# Lab_Controller_Board_v09.net
KiCad netlist of a schematic drawn in EAGLE
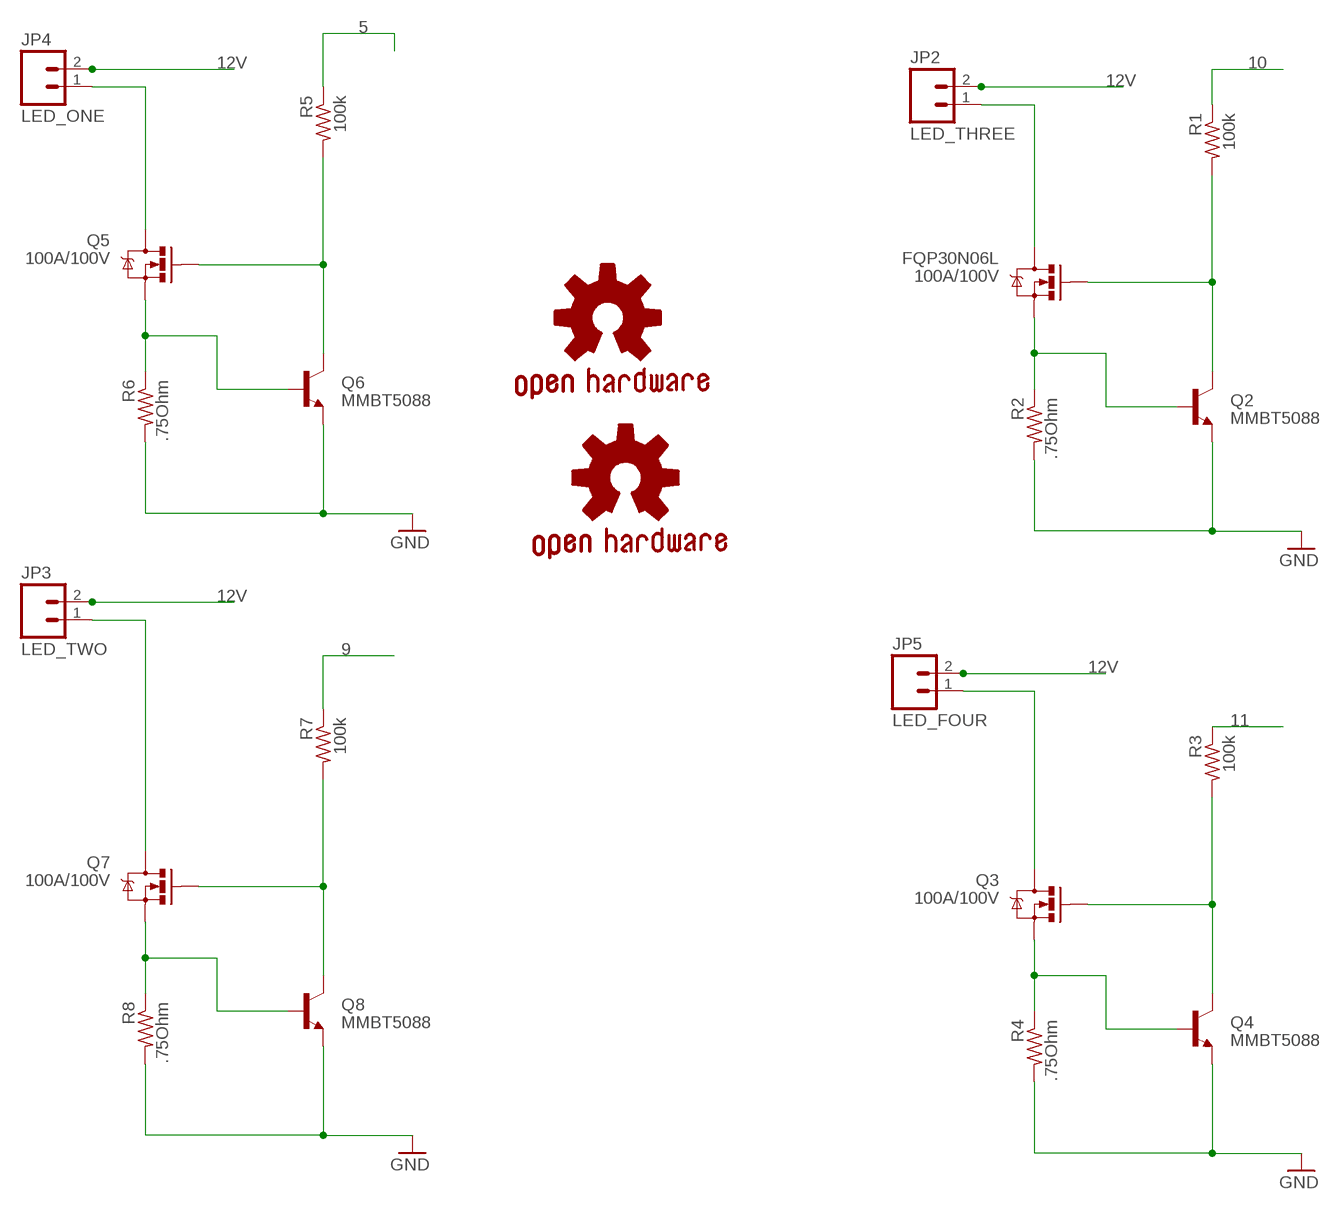
[diagram p0: schematic, sheet 1]
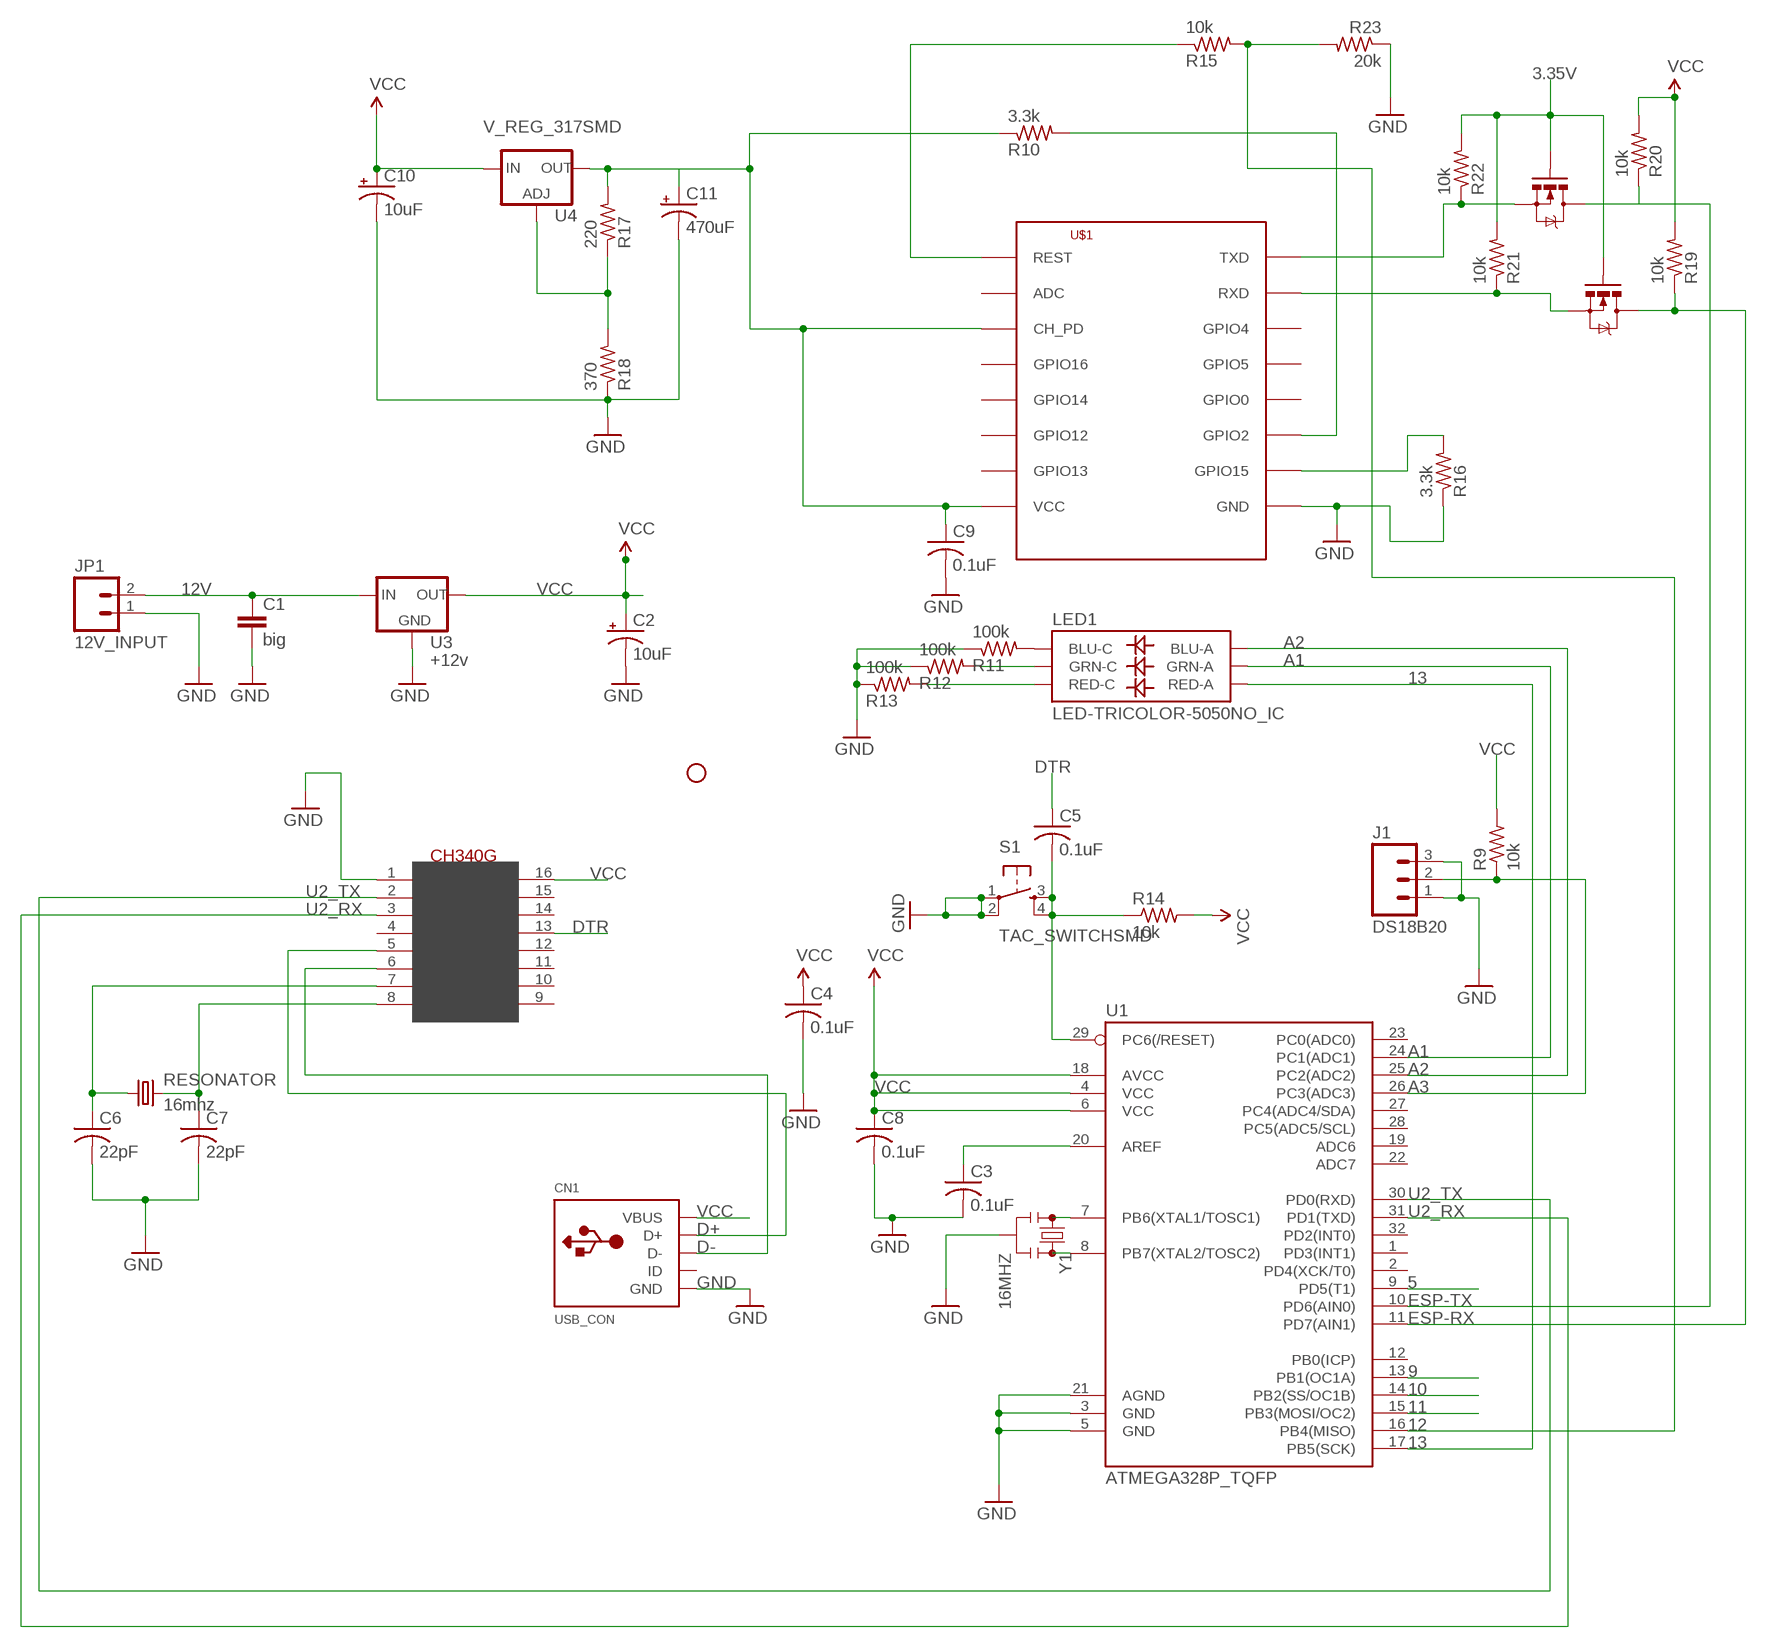
[diagram p1: schematic, sheet 2]

(export (version "E")
  (design (tool "Eeschema 10.0.6"))
  (components
    (comp (ref "C1")
      (value "big")
      (footprint "eagle-import:CAP-PTH-5MM")
      (libsource (lib "eagle-import") (part "CAPPTH1"))
    )
    (comp (ref "C2")
      (value "10uF")
      (footprint "eagle-import:EIA3528")
      (libsource (lib "eagle-import") (part "CAP_POL3528"))
    )
    (comp (ref "C3")
      (value "0.1uF")
      (footprint "eagle-import:C0402")
      (libsource (lib "eagle-import") (part "C-USC0402"))
    )
    (comp (ref "C4")
      (value "0.1uF")
      (footprint "eagle-import:C0805K")
      (libsource (lib "eagle-import") (part "C-USC0805K"))
    )
    (comp (ref "C5")
      (value "0.1uF")
      (footprint "eagle-import:C0805K")
      (libsource (lib "eagle-import") (part "C-USC0805K"))
    )
    (comp (ref "C6")
      (value "22pF")
      (footprint "eagle-import:C0805K")
      (libsource (lib "eagle-import") (part "C-USC0805K"))
    )
    (comp (ref "C7")
      (value "22pF")
      (footprint "eagle-import:C0805K")
      (libsource (lib "eagle-import") (part "C-USC0805K"))
    )
    (comp (ref "C8")
      (value "0.1uF")
      (footprint "eagle-import:C0402")
      (libsource (lib "eagle-import") (part "C-USC0402"))
    )
    (comp (ref "C9")
      (value "0.1uF")
      (footprint "eagle-import:C0805K")
      (libsource (lib "eagle-import") (part "C-USC0805K"))
    )
    (comp (ref "C10")
      (value "10uF")
      (footprint "eagle-import:EIA3528")
      (libsource (lib "eagle-import") (part "CAP_POL3528"))
    )
    (comp (ref "C11")
      (value "470uF")
      (footprint "eagle-import:D_7343-31W")
      (libsource (lib "eagle-import") (part "CPOL-USD/7343-31W"))
    )
    (comp (ref "CN1")
      (value "USB_CON")
      (footprint "eagle-import:USB-MINIB")
      (libsource (lib "eagle-import") (part "USBMINIB"))
    )
    (comp (ref "J1")
      (value "DS18B20")
      (footprint "eagle-import:1X03_LOCK")
      (libsource (lib "eagle-import") (part "M03LOCK"))
    )
    (comp (ref "JP1")
      (value "12V_INPUT")
      (footprint "eagle-import:SCREWTERMINAL-5MM-2")
      (libsource (lib "eagle-import") (part "M025MM"))
    )
    (comp (ref "LED1")
      (value "LED-TRICOLOR-5050NO_IC")
      (footprint "eagle-import:LED-TRICOLOR-5050")
      (libsource (lib "eagle-import") (part "LED-TRICOLOR-5050NO_IC"))
    )
    (comp (ref "Q1")
      (value "MOSFET-NCHANNELAO3404A")
      (footprint "eagle-import:SOT23-3")
      (libsource (lib "eagle-import") (part "MOSFET-NCHANNELAO3404A"))
    )
    (comp (ref "Q9")
      (value "MOSFET-NCHANNELAO3404A")
      (footprint "eagle-import:SOT23-3")
      (libsource (lib "eagle-import") (part "MOSFET-NCHANNELAO3404A"))
    )
    (comp (ref "R9")
      (value "10k")
      (footprint "eagle-import:R0805W")
      (libsource (lib "eagle-import") (part "R-US_R0805W"))
    )
    (comp (ref "R10")
      (value "3.3k")
      (footprint "eagle-import:R0805W")
      (libsource (lib "eagle-import") (part "R-US_R0805W"))
    )
    (comp (ref "R11")
      (value "100k")
      (footprint "eagle-import:R0805W")
      (libsource (lib "eagle-import") (part "R-US_R0805W"))
    )
    (comp (ref "R12")
      (value "100k")
      (footprint "eagle-import:R0805W")
      (libsource (lib "eagle-import") (part "R-US_R0805W"))
    )
    (comp (ref "R13")
      (value "100k")
      (footprint "eagle-import:R0805W")
      (libsource (lib "eagle-import") (part "R-US_R0805W"))
    )
    (comp (ref "R14")
      (value "10k")
      (footprint "eagle-import:R0805W")
      (libsource (lib "eagle-import") (part "R-US_R0805W"))
    )
    (comp (ref "R15")
      (value "10k")
      (footprint "eagle-import:R0805W")
      (libsource (lib "eagle-import") (part "R-US_R0805W"))
    )
    (comp (ref "R16")
      (value "3.3k")
      (footprint "eagle-import:R0805W")
      (libsource (lib "eagle-import") (part "R-US_R0805W"))
    )
    (comp (ref "R17")
      (value "220")
      (footprint "eagle-import:R0805W")
      (libsource (lib "eagle-import") (part "R-US_R0805W"))
    )
    (comp (ref "R18")
      (value "370")
      (footprint "eagle-import:R0805W")
      (libsource (lib "eagle-import") (part "R-US_R0805W"))
    )
    (comp (ref "R19")
      (value "10k")
      (footprint "eagle-import:R0805W")
      (libsource (lib "eagle-import") (part "R-US_R0805W"))
    )
    (comp (ref "R20")
      (value "10k")
      (footprint "eagle-import:R0805W")
      (libsource (lib "eagle-import") (part "R-US_R0805W"))
    )
    (comp (ref "R21")
      (value "10k")
      (footprint "eagle-import:R0805W")
      (libsource (lib "eagle-import") (part "R-US_R0805W"))
    )
    (comp (ref "R22")
      (value "10k")
      (footprint "eagle-import:R0805W")
      (libsource (lib "eagle-import") (part "R-US_R0805W"))
    )
    (comp (ref "R23")
      (value "20k")
      (footprint "eagle-import:R0805W")
      (libsource (lib "eagle-import") (part "R-US_R0805W"))
    )
    (comp (ref "RESONATOR")
      (value "16mhz")
      (footprint "eagle-import:HC49UP")
      (libsource (lib "eagle-import") (part "CRYSTALHC49UP"))
    )
    (comp (ref "S1")
      (value "TAC_SWITCHSMD")
      (footprint "eagle-import:TACTILE-SWITCH-SMD")
      (libsource (lib "eagle-import") (part "TAC_SWITCHSMD"))
    )
    (comp (ref "STANDOFF1")
      (value "STAND-OFF")
      (footprint "eagle-import:STAND-OFF")
      (libsource (lib "eagle-import") (part "STAND-OFF"))
    )
    (comp (ref "U$1")
      (value "ESP8266-07")
      (footprint "eagle-import:ESP-07")
      (libsource (lib "eagle-import") (part "ESP8266-07"))
    )
    (comp (ref "U1")
      (value "ATMEGA328P_TQFP")
      (footprint "eagle-import:TQFP32-08")
      (libsource (lib "eagle-import") (part "ATMEGA328P_TQFP"))
    )
    (comp (ref "U2")
      (value "CH340G")
      (footprint "eagle-import:SOIC16")
      (libsource (lib "eagle-import") (part "CH340G"))
    )
    (comp (ref "U3")
      (value "+12v")
      (footprint "eagle-import:TO-252")
      (libsource (lib "eagle-import") (part "V_REG_78XX7812"))
    )
    (comp (ref "U4")
      (value "V_REG_317SMD")
      (footprint "eagle-import:SOT223")
      (libsource (lib "eagle-import") (part "V_REG_317SMD"))
    )
    (comp (ref "Y1")
      (value "16MHZ")
      (footprint "eagle-import:RESONATOR-SMD")
      (libsource (lib "eagle-import") (part "RESONATOR16MHZ"))
    )
    (comp (ref "FQP30N06L")
      (value "100A/100V")
      (footprint "eagle-import:TO-263_D2PAK")
      (libsource (lib "eagle-import") (part "MOSFET-NCHANNELPSMN7R0"))
    )
    (comp (ref "GOLD_ORB_SM1")
      (value "OSHWLOGO_GOLD_ORB_MED")
      (footprint "eagle-import:OSHW1")
      (libsource (lib "eagle-import") (part "OSHWLOGO_GOLD_ORB_MED"))
    )
    (comp (ref "GOLD_ORB_SM2")
      (value "OSHWLOGO_GOLD_ORB_SM")
      (footprint "eagle-import:OSHW2")
      (libsource (lib "eagle-import") (part "OSHWLOGO_GOLD_ORB_SM"))
    )
    (comp (ref "JP2")
      (value "LED_THREE")
      (footprint "eagle-import:SCREWTERMINAL-5MM-2")
      (libsource (lib "eagle-import") (part "M025MM"))
    )
    (comp (ref "JP3")
      (value "LED_TWO")
      (footprint "eagle-import:SCREWTERMINAL-5MM-2")
      (libsource (lib "eagle-import") (part "M025MM"))
    )
    (comp (ref "JP4")
      (value "LED_ONE")
      (footprint "eagle-import:SCREWTERMINAL-5MM-2")
      (libsource (lib "eagle-import") (part "M025MM"))
    )
    (comp (ref "JP5")
      (value "LED_FOUR")
      (footprint "eagle-import:SCREWTERMINAL-5MM-2")
      (libsource (lib "eagle-import") (part "M025MM"))
    )
    (comp (ref "Q2")
      (value "MMBT5088")
      (footprint "eagle-import:SOT23-3")
      (libsource (lib "eagle-import") (part "TRANSISTOR_NPNMMBT5088"))
    )
    (comp (ref "Q3")
      (value "100A/100V")
      (footprint "eagle-import:TO-263_D2PAK")
      (libsource (lib "eagle-import") (part "MOSFET-NCHANNELPSMN7R0"))
    )
    (comp (ref "Q4")
      (value "MMBT5088")
      (footprint "eagle-import:SOT23-3")
      (libsource (lib "eagle-import") (part "TRANSISTOR_NPNMMBT5088"))
    )
    (comp (ref "Q5")
      (value "100A/100V")
      (footprint "eagle-import:TO-263_D2PAK")
      (libsource (lib "eagle-import") (part "MOSFET-NCHANNELPSMN7R0"))
    )
    (comp (ref "Q6")
      (value "MMBT5088")
      (footprint "eagle-import:SOT23-3")
      (libsource (lib "eagle-import") (part "TRANSISTOR_NPNMMBT5088"))
    )
    (comp (ref "Q7")
      (value "100A/100V")
      (footprint "eagle-import:TO-263_D2PAK")
      (libsource (lib "eagle-import") (part "MOSFET-NCHANNELPSMN7R0"))
    )
    (comp (ref "Q8")
      (value "MMBT5088")
      (footprint "eagle-import:SOT23-3")
      (libsource (lib "eagle-import") (part "TRANSISTOR_NPNMMBT5088"))
    )
    (comp (ref "R1")
      (value "100k")
      (footprint "eagle-import:R0805W")
      (libsource (lib "eagle-import") (part "R-US_R0805W"))
    )
    (comp (ref "R2")
      (value ".75Ohm")
      (footprint "eagle-import:0411V")
      (libsource (lib "eagle-import") (part "R-US_0411/3V"))
    )
    (comp (ref "R3")
      (value "100k")
      (footprint "eagle-import:R0805W")
      (libsource (lib "eagle-import") (part "R-US_R0805W"))
    )
    (comp (ref "R4")
      (value ".75Ohm")
      (footprint "eagle-import:0411V")
      (libsource (lib "eagle-import") (part "R-US_0411/3V"))
    )
    (comp (ref "R5")
      (value "100k")
      (footprint "eagle-import:R0805W")
      (libsource (lib "eagle-import") (part "R-US_R0805W"))
    )
    (comp (ref "R6")
      (value ".75Ohm")
      (footprint "eagle-import:0411V")
      (libsource (lib "eagle-import") (part "R-US_0411/3V"))
    )
    (comp (ref "R7")
      (value "100k")
      (footprint "eagle-import:R0805W")
      (libsource (lib "eagle-import") (part "R-US_R0805W"))
    )
    (comp (ref "R8")
      (value ".75Ohm")
      (footprint "eagle-import:0411V")
      (libsource (lib "eagle-import") (part "R-US_0411/3V"))
    )
  )
  (nets
    (net (code "1") (name "3.35V") (class "Default")
      (node (ref "C11") (pin "+") (pinfunction "+_+") (pintype "passive"))
      (node (ref "C9") (pin "1") (pinfunction "1_1") (pintype "passive"))
      (node (ref "Q1") (pin "1") (pinfunction "G_1") (pintype "passive"))
      (node (ref "Q9") (pin "1") (pinfunction "G_1") (pintype "passive"))
      (node (ref "R10") (pin "1") (pinfunction "1_1") (pintype "passive"))
      (node (ref "R17") (pin "2") (pinfunction "2_2") (pintype "passive"))
      (node (ref "R21") (pin "2") (pinfunction "2_2") (pintype "passive"))
      (node (ref "R22") (pin "2") (pinfunction "2_2") (pintype "passive"))
      (node (ref "U$1") (pin "CH_PD") (pinfunction "CH_PD_CH_PD") (pintype "input"))
      (node (ref "U$1") (pin "VCC") (pinfunction "VCC_VCC") (pintype "power_in"))
      (node (ref "U4") (pin "2") (pinfunction "OUT_2") (pintype "output"))
    )
    (net (code "2") (name "5") (class "Default")
      (node (ref "R5") (pin "1") (pinfunction "1_1") (pintype "passive"))
      (node (ref "U1") (pin "9") (pinfunction "PD5(T1)_9") (pintype "bidirectional"))
    )
    (net (code "3") (name "9") (class "Default")
      (node (ref "R7") (pin "1") (pinfunction "1_1") (pintype "passive"))
      (node (ref "U1") (pin "13") (pinfunction "PB1(OC1A)_13") (pintype "bidirectional"))
    )
    (net (code "4") (name "10") (class "Default")
      (node (ref "R1") (pin "1") (pinfunction "1_1") (pintype "passive"))
      (node (ref "U1") (pin "14") (pinfunction "PB2(SS/OC1B)_14") (pintype "bidirectional"))
    )
    (net (code "5") (name "11") (class "Default")
      (node (ref "R3") (pin "1") (pinfunction "1_1") (pintype "passive"))
      (node (ref "U1") (pin "15") (pinfunction "PB3(MOSI/OC2)_15") (pintype "bidirectional"))
    )
    (net (code "6") (name "12") (class "Default")
      (node (ref "R15") (pin "2") (pinfunction "2_2") (pintype "passive"))
      (node (ref "R23") (pin "2") (pinfunction "2_2") (pintype "passive"))
      (node (ref "U1") (pin "16") (pinfunction "PB4(MISO)_16") (pintype "bidirectional"))
    )
    (net (code "7") (name "12V") (class "Default")
      (node (ref "C1") (pin "1") (pinfunction "1_1") (pintype "passive"))
      (node (ref "JP1") (pin "2") (pinfunction "2_2") (pintype "passive"))
      (node (ref "JP2") (pin "2") (pinfunction "2_2") (pintype "passive"))
      (node (ref "JP3") (pin "2") (pinfunction "2_2") (pintype "passive"))
      (node (ref "JP4") (pin "2") (pinfunction "2_2") (pintype "passive"))
      (node (ref "JP5") (pin "2") (pinfunction "2_2") (pintype "passive"))
      (node (ref "U3") (pin "1") (pinfunction "IN_1") (pintype "input"))
    )
    (net (code "8") (name "13") (class "Default")
      (node (ref "LED1") (pin "2") (pinfunction "RED-A_2") (pintype "bidirectional"))
      (node (ref "U1") (pin "17") (pinfunction "PB5(SCK)_17") (pintype "bidirectional"))
    )
    (net (code "9") (name "A1") (class "Default")
      (node (ref "LED1") (pin "1") (pinfunction "GRN-A_1") (pintype "bidirectional"))
      (node (ref "U1") (pin "24") (pinfunction "PC1(ADC1)_24") (pintype "bidirectional"))
    )
    (net (code "10") (name "A2") (class "Default")
      (node (ref "LED1") (pin "3") (pinfunction "BLU-A_3") (pintype "bidirectional"))
      (node (ref "U1") (pin "25") (pinfunction "PC2(ADC2)_25") (pintype "bidirectional"))
    )
    (net (code "11") (name "A3") (class "Default")
      (node (ref "J1") (pin "2") (pinfunction "2_2") (pintype "passive"))
      (node (ref "R9") (pin "1") (pinfunction "1_1") (pintype "passive"))
      (node (ref "U1") (pin "26") (pinfunction "PC3(ADC3)_26") (pintype "bidirectional"))
    )
    (net (code "12") (name "D+") (class "Default")
      (node (ref "CN1") (pin "D+") (pinfunction "D+_D+") (pintype "bidirectional"))
      (node (ref "U2") (pin "5") (pinfunction "D+_5") (pintype "bidirectional"))
    )
    (net (code "13") (name "D-") (class "Default")
      (node (ref "CN1") (pin "D-") (pinfunction "D-_D-") (pintype "bidirectional"))
      (node (ref "U2") (pin "6") (pinfunction "D-_6") (pintype "bidirectional"))
    )
    (net (code "14") (name "DTR") (class "Default")
      (node (ref "C5") (pin "1") (pinfunction "1_1") (pintype "passive"))
      (node (ref "U2") (pin "13") (pinfunction "DTR_13") (pintype "bidirectional"))
    )
    (net (code "15") (name "ESP-RX") (class "Default")
      (node (ref "Q9") (pin "3") (pinfunction "D_3") (pintype "passive"))
      (node (ref "R19") (pin "1") (pinfunction "1_1") (pintype "passive"))
      (node (ref "U1") (pin "11") (pinfunction "PD7(AIN1)_11") (pintype "bidirectional"))
    )
    (net (code "16") (name "ESP-TX") (class "Default")
      (node (ref "Q1") (pin "3") (pinfunction "D_3") (pintype "passive"))
      (node (ref "R20") (pin "1") (pinfunction "1_1") (pintype "passive"))
      (node (ref "U1") (pin "10") (pinfunction "PD6(AIN0)_10") (pintype "bidirectional"))
    )
    (net (code "17") (name "GND") (class "Default")
      (node (ref "C1") (pin "2") (pinfunction "2_2") (pintype "passive"))
      (node (ref "C10") (pin "C") (pinfunction "-_C") (pintype "passive"))
      (node (ref "C11") (pin "-") (pinfunction "-_-") (pintype "passive"))
      (node (ref "C2") (pin "C") (pinfunction "-_C") (pintype "passive"))
      (node (ref "C3") (pin "2") (pinfunction "2_2") (pintype "passive"))
      (node (ref "C4") (pin "2") (pinfunction "2_2") (pintype "passive"))
      (node (ref "C6") (pin "2") (pinfunction "2_2") (pintype "passive"))
      (node (ref "C7") (pin "2") (pinfunction "2_2") (pintype "passive"))
      (node (ref "C8") (pin "2") (pinfunction "2_2") (pintype "passive"))
      (node (ref "C9") (pin "2") (pinfunction "2_2") (pintype "passive"))
      (node (ref "CN1") (pin "GND") (pinfunction "GND_GND") (pintype "power_in"))
      (node (ref "J1") (pin "1") (pinfunction "1_1") (pintype "passive"))
      (node (ref "J1") (pin "3") (pinfunction "3_3") (pintype "passive"))
      (node (ref "JP1") (pin "1") (pinfunction "1_1") (pintype "passive"))
      (node (ref "Q2") (pin "2") (pinfunction "E_2") (pintype "passive"))
      (node (ref "Q4") (pin "2") (pinfunction "E_2") (pintype "passive"))
      (node (ref "Q6") (pin "2") (pinfunction "E_2") (pintype "passive"))
      (node (ref "Q8") (pin "2") (pinfunction "E_2") (pintype "passive"))
      (node (ref "R11") (pin "1") (pinfunction "1_1") (pintype "passive"))
      (node (ref "R12") (pin "1") (pinfunction "1_1") (pintype "passive"))
      (node (ref "R13") (pin "1") (pinfunction "1_1") (pintype "passive"))
      (node (ref "R16") (pin "1") (pinfunction "1_1") (pintype "passive"))
      (node (ref "R18") (pin "1") (pinfunction "1_1") (pintype "passive"))
      (node (ref "R2") (pin "2") (pinfunction "2_2") (pintype "passive"))
      (node (ref "R23") (pin "1") (pinfunction "1_1") (pintype "passive"))
      (node (ref "R4") (pin "2") (pinfunction "2_2") (pintype "passive"))
      (node (ref "R6") (pin "2") (pinfunction "2_2") (pintype "passive"))
      (node (ref "R8") (pin "2") (pinfunction "2_2") (pintype "passive"))
      (node (ref "S1") (pin "1") (pinfunction "1_1") (pintype "passive"))
      (node (ref "S1") (pin "2") (pinfunction "2_2") (pintype "passive"))
      (node (ref "U$1") (pin "GND") (pinfunction "GND_GND") (pintype "power_in"))
      (node (ref "U1") (pin "21") (pinfunction "AGND_21") (pintype "bidirectional"))
      (node (ref "U1") (pin "3") (pinfunction "GND_3") (pintype "bidirectional"))
      (node (ref "U1") (pin "5") (pinfunction "GND_5") (pintype "bidirectional"))
      (node (ref "U2") (pin "1") (pinfunction "GND_1") (pintype "bidirectional"))
      (node (ref "U3") (pin "3") (pinfunction "GND_3") (pintype "input"))
      (node (ref "Y1") (pin "2") (pinfunction "2_2") (pintype "passive"))
    )
    (net (code "18") (name "Net-(FQP30N06L-D)") (class "Default")
      (node (ref "FQP30N06L") (pin "2") (pinfunction "D_2") (pintype "passive"))
      (node (ref "JP2") (pin "1") (pinfunction "1_1") (pintype "passive"))
    )
    (net (code "19") (name "Net-(FQP30N06L-G)") (class "Default")
      (node (ref "FQP30N06L") (pin "1") (pinfunction "G_1") (pintype "passive"))
      (node (ref "Q2") (pin "3") (pinfunction "C_3") (pintype "passive"))
      (node (ref "R1") (pin "2") (pinfunction "2_2") (pintype "passive"))
    )
    (net (code "20") (name "Net-(FQP30N06L-S)") (class "Default")
      (node (ref "FQP30N06L") (pin "3") (pinfunction "S_3") (pintype "passive"))
      (node (ref "Q2") (pin "1") (pinfunction "B_1") (pintype "passive"))
      (node (ref "R2") (pin "1") (pinfunction "1_1") (pintype "passive"))
    )
    (net (code "21") (name "Net-(LED1-BLU-C)") (class "Default")
      (node (ref "LED1") (pin "4") (pinfunction "BLU-C_4") (pintype "bidirectional"))
      (node (ref "R11") (pin "2") (pinfunction "2_2") (pintype "passive"))
    )
    (net (code "22") (name "Net-(LED1-GRN-C)") (class "Default")
      (node (ref "LED1") (pin "6") (pinfunction "GRN-C_6") (pintype "bidirectional"))
      (node (ref "R12") (pin "2") (pinfunction "2_2") (pintype "passive"))
    )
    (net (code "23") (name "Net-(LED1-RED-C)") (class "Default")
      (node (ref "LED1") (pin "5") (pinfunction "RED-C_5") (pintype "bidirectional"))
      (node (ref "R13") (pin "2") (pinfunction "2_2") (pintype "passive"))
    )
    (net (code "24") (name "Net-(Q1-S)") (class "Default")
      (node (ref "Q1") (pin "2") (pinfunction "S_2") (pintype "passive"))
      (node (ref "R22") (pin "1") (pinfunction "1_1") (pintype "passive"))
      (node (ref "U$1") (pin "TXD") (pinfunction "TXD_TXD") (pintype "output"))
    )
    (net (code "25") (name "Net-(Q3-D)") (class "Default")
      (node (ref "JP5") (pin "1") (pinfunction "1_1") (pintype "passive"))
      (node (ref "Q3") (pin "2") (pinfunction "D_2") (pintype "passive"))
    )
    (net (code "26") (name "Net-(Q3-G)") (class "Default")
      (node (ref "Q3") (pin "1") (pinfunction "G_1") (pintype "passive"))
      (node (ref "Q4") (pin "3") (pinfunction "C_3") (pintype "passive"))
      (node (ref "R3") (pin "2") (pinfunction "2_2") (pintype "passive"))
    )
    (net (code "27") (name "Net-(Q3-S)") (class "Default")
      (node (ref "Q3") (pin "3") (pinfunction "S_3") (pintype "passive"))
      (node (ref "Q4") (pin "1") (pinfunction "B_1") (pintype "passive"))
      (node (ref "R4") (pin "1") (pinfunction "1_1") (pintype "passive"))
    )
    (net (code "28") (name "Net-(Q5-D)") (class "Default")
      (node (ref "JP4") (pin "1") (pinfunction "1_1") (pintype "passive"))
      (node (ref "Q5") (pin "2") (pinfunction "D_2") (pintype "passive"))
    )
    (net (code "29") (name "Net-(Q5-G)") (class "Default")
      (node (ref "Q5") (pin "1") (pinfunction "G_1") (pintype "passive"))
      (node (ref "Q6") (pin "3") (pinfunction "C_3") (pintype "passive"))
      (node (ref "R5") (pin "2") (pinfunction "2_2") (pintype "passive"))
    )
    (net (code "30") (name "Net-(Q5-S)") (class "Default")
      (node (ref "Q5") (pin "3") (pinfunction "S_3") (pintype "passive"))
      (node (ref "Q6") (pin "1") (pinfunction "B_1") (pintype "passive"))
      (node (ref "R6") (pin "1") (pinfunction "1_1") (pintype "passive"))
    )
    (net (code "31") (name "Net-(Q7-D)") (class "Default")
      (node (ref "JP3") (pin "1") (pinfunction "1_1") (pintype "passive"))
      (node (ref "Q7") (pin "2") (pinfunction "D_2") (pintype "passive"))
    )
    (net (code "32") (name "Net-(Q7-G)") (class "Default")
      (node (ref "Q7") (pin "1") (pinfunction "G_1") (pintype "passive"))
      (node (ref "Q8") (pin "3") (pinfunction "C_3") (pintype "passive"))
      (node (ref "R7") (pin "2") (pinfunction "2_2") (pintype "passive"))
    )
    (net (code "33") (name "Net-(Q7-S)") (class "Default")
      (node (ref "Q7") (pin "3") (pinfunction "S_3") (pintype "passive"))
      (node (ref "Q8") (pin "1") (pinfunction "B_1") (pintype "passive"))
      (node (ref "R8") (pin "1") (pinfunction "1_1") (pintype "passive"))
    )
    (net (code "34") (name "Net-(Q9-S)") (class "Default")
      (node (ref "Q9") (pin "2") (pinfunction "S_2") (pintype "passive"))
      (node (ref "R21") (pin "1") (pinfunction "1_1") (pintype "passive"))
      (node (ref "U$1") (pin "RXD") (pinfunction "RXD_RXD") (pintype "input"))
    )
    (net (code "35") (name "Net-(R10-Pad2)") (class "Default")
      (node (ref "R10") (pin "2") (pinfunction "2_2") (pintype "passive"))
      (node (ref "U$1") (pin "GPIO2") (pinfunction "GPIO2_GPIO2") (pintype "bidirectional"))
    )
    (net (code "36") (name "Net-(R15-Pad1)") (class "Default")
      (node (ref "R15") (pin "1") (pinfunction "1_1") (pintype "passive"))
      (node (ref "U$1") (pin "REST") (pinfunction "REST_REST") (pintype "bidirectional"))
    )
    (net (code "37") (name "Net-(R16-Pad2)") (class "Default")
      (node (ref "R16") (pin "2") (pinfunction "2_2") (pintype "passive"))
      (node (ref "U$1") (pin "GPIO15") (pinfunction "GPIO15_GPIO15") (pintype "input"))
    )
    (net (code "38") (name "Net-(U1-AREF)") (class "Default")
      (node (ref "C3") (pin "1") (pinfunction "1_1") (pintype "passive"))
      (node (ref "U1") (pin "20") (pinfunction "AREF_20") (pintype "bidirectional"))
    )
    (net (code "39") (name "Net-(U1-PB6(XTAL1{slash}TOSC1))") (class "Default")
      (node (ref "U1") (pin "7") (pinfunction "PB6(XTAL1/TOSC1)_7") (pintype "bidirectional"))
      (node (ref "Y1") (pin "1") (pinfunction "1_1") (pintype "passive"))
    )
    (net (code "40") (name "Net-(U1-PB7(XTAL2{slash}TOSC2))") (class "Default")
      (node (ref "U1") (pin "8") (pinfunction "PB7(XTAL2/TOSC2)_8") (pintype "bidirectional"))
      (node (ref "Y1") (pin "3") (pinfunction "3_3") (pintype "passive"))
    )
    (net (code "41") (name "Net-(U1-PC6({slash}RESET))") (class "Default")
      (node (ref "C5") (pin "2") (pinfunction "2_2") (pintype "passive"))
      (node (ref "R14") (pin "1") (pinfunction "1_1") (pintype "passive"))
      (node (ref "S1") (pin "3") (pinfunction "3_3") (pintype "passive"))
      (node (ref "S1") (pin "4") (pinfunction "4_4") (pintype "passive"))
      (node (ref "U1") (pin "29") (pinfunction "PC6(/RESET)_29") (pintype "bidirectional"))
    )
    (net (code "42") (name "Net-(U2-XI)") (class "Default")
      (node (ref "C6") (pin "1") (pinfunction "1_1") (pintype "passive"))
      (node (ref "RESONATOR") (pin "1") (pinfunction "1_1") (pintype "passive"))
      (node (ref "U2") (pin "7") (pinfunction "XI_7") (pintype "bidirectional"))
    )
    (net (code "43") (name "Net-(U2-XO)") (class "Default")
      (node (ref "C7") (pin "1") (pinfunction "1_1") (pintype "passive"))
      (node (ref "RESONATOR") (pin "2") (pinfunction "2_2") (pintype "passive"))
      (node (ref "U2") (pin "8") (pinfunction "XO_8") (pintype "bidirectional"))
    )
    (net (code "44") (name "Net-(U4-ADJ)") (class "Default")
      (node (ref "R17") (pin "1") (pinfunction "1_1") (pintype "passive"))
      (node (ref "R18") (pin "2") (pinfunction "2_2") (pintype "passive"))
      (node (ref "U4") (pin "1") (pinfunction "ADJ_1") (pintype "input"))
    )
    (net (code "45") (name "U2_RX") (class "Default")
      (node (ref "U1") (pin "31") (pinfunction "PD1(TXD)_31") (pintype "bidirectional"))
      (node (ref "U2") (pin "3") (pinfunction "RX_3") (pintype "bidirectional"))
    )
    (net (code "46") (name "U2_TX") (class "Default")
      (node (ref "U1") (pin "30") (pinfunction "PD0(RXD)_30") (pintype "bidirectional"))
      (node (ref "U2") (pin "2") (pinfunction "TX_2") (pintype "bidirectional"))
    )
    (net (code "47") (name "VCC") (class "Default")
      (node (ref "C10") (pin "A") (pinfunction "+_A") (pintype "passive"))
      (node (ref "C2") (pin "A") (pinfunction "+_A") (pintype "passive"))
      (node (ref "C4") (pin "1") (pinfunction "1_1") (pintype "passive"))
      (node (ref "C8") (pin "1") (pinfunction "1_1") (pintype "passive"))
      (node (ref "CN1") (pin "VBUS") (pinfunction "VBUS_VBUS") (pintype "power_in"))
      (node (ref "R14") (pin "2") (pinfunction "2_2") (pintype "passive"))
      (node (ref "R19") (pin "2") (pinfunction "2_2") (pintype "passive"))
      (node (ref "R20") (pin "2") (pinfunction "2_2") (pintype "passive"))
      (node (ref "R9") (pin "2") (pinfunction "2_2") (pintype "passive"))
      (node (ref "U1") (pin "18") (pinfunction "AVCC_18") (pintype "bidirectional"))
      (node (ref "U1") (pin "4") (pinfunction "VCC_4") (pintype "bidirectional"))
      (node (ref "U1") (pin "6") (pinfunction "VCC_6") (pintype "bidirectional"))
      (node (ref "U2") (pin "16") (pinfunction "VCC_16") (pintype "bidirectional"))
      (node (ref "U3") (pin "2") (pinfunction "OUT_2") (pintype "passive"))
      (node (ref "U4") (pin "3") (pinfunction "IN_3") (pintype "input"))
    )
    (net (code "48") (name "unconnected-(CN1-PadID)") (class "Default")
      (node (ref "CN1") (pin "ID") (pinfunction "ID_ID") (pintype "bidirectional"))
    )
    (net (code "49") (name "unconnected-(U$1-PadADC)") (class "Default")
      (node (ref "U$1") (pin "ADC") (pinfunction "ADC_ADC") (pintype "bidirectional"))
    )
    (net (code "50") (name "unconnected-(U$1-PadGPIO0)") (class "Default")
      (node (ref "U$1") (pin "GPIO0") (pinfunction "GPIO0_GPIO0") (pintype "bidirectional"))
    )
    (net (code "51") (name "unconnected-(U$1-PadGPIO4)") (class "Default")
      (node (ref "U$1") (pin "GPIO4") (pinfunction "GPIO4_GPIO4") (pintype "bidirectional"))
    )
    (net (code "52") (name "unconnected-(U$1-PadGPIO5)") (class "Default")
      (node (ref "U$1") (pin "GPIO5") (pinfunction "GPIO5_GPIO5") (pintype "bidirectional"))
    )
    (net (code "53") (name "unconnected-(U$1-PadGPIO12)") (class "Default")
      (node (ref "U$1") (pin "GPIO12") (pinfunction "GPIO12_GPIO12") (pintype "bidirectional"))
    )
    (net (code "54") (name "unconnected-(U$1-PadGPIO13)") (class "Default")
      (node (ref "U$1") (pin "GPIO13") (pinfunction "GPIO13_GPIO13") (pintype "bidirectional"))
    )
    (net (code "55") (name "unconnected-(U$1-PadGPIO14)") (class "Default")
      (node (ref "U$1") (pin "GPIO14") (pinfunction "GPIO14_GPIO14") (pintype "bidirectional"))
    )
    (net (code "56") (name "unconnected-(U$1-PadGPIO16)") (class "Default")
      (node (ref "U$1") (pin "GPIO16") (pinfunction "GPIO16_GPIO16") (pintype "bidirectional"))
    )
    (net (code "57") (name "unconnected-(U1-ADC6-Pad19)") (class "Default")
      (node (ref "U1") (pin "19") (pinfunction "ADC6_19") (pintype "bidirectional"))
    )
    (net (code "58") (name "unconnected-(U1-ADC7-Pad22)") (class "Default")
      (node (ref "U1") (pin "22") (pinfunction "ADC7_22") (pintype "bidirectional"))
    )
    (net (code "59") (name "unconnected-(U1-PB0(ICP)-Pad12)") (class "Default")
      (node (ref "U1") (pin "12") (pinfunction "PB0(ICP)_12") (pintype "bidirectional"))
    )
    (net (code "60") (name "unconnected-(U1-PC0(ADC0)-Pad23)") (class "Default")
      (node (ref "U1") (pin "23") (pinfunction "PC0(ADC0)_23") (pintype "bidirectional"))
    )
    (net (code "61") (name "unconnected-(U1-PC4(ADC4{slash}SDA)-Pad27)") (class "Default")
      (node (ref "U1") (pin "27") (pinfunction "PC4(ADC4/SDA)_27") (pintype "bidirectional"))
    )
    (net (code "62") (name "unconnected-(U1-PC5(ADC5{slash}SCL)-Pad28)") (class "Default")
      (node (ref "U1") (pin "28") (pinfunction "PC5(ADC5/SCL)_28") (pintype "bidirectional"))
    )
    (net (code "63") (name "unconnected-(U1-PD2(INT0)-Pad32)") (class "Default")
      (node (ref "U1") (pin "32") (pinfunction "PD2(INT0)_32") (pintype "bidirectional"))
    )
    (net (code "64") (name "unconnected-(U1-PD3(INT1)-Pad1)") (class "Default")
      (node (ref "U1") (pin "1") (pinfunction "PD3(INT1)_1") (pintype "bidirectional"))
    )
    (net (code "65") (name "unconnected-(U1-PD4(XCK{slash}T0)-Pad2)") (class "Default")
      (node (ref "U1") (pin "2") (pinfunction "PD4(XCK/T0)_2") (pintype "bidirectional"))
    )
    (net (code "66") (name "unconnected-(U2-CTS-Pad9)") (class "Default")
      (node (ref "U2") (pin "9") (pinfunction "CTS_9") (pintype "bidirectional"))
    )
    (net (code "67") (name "unconnected-(U2-DCD-Pad12)") (class "Default")
      (node (ref "U2") (pin "12") (pinfunction "DCD_12") (pintype "bidirectional"))
    )
    (net (code "68") (name "unconnected-(U2-DSR-Pad10)") (class "Default")
      (node (ref "U2") (pin "10") (pinfunction "DSR_10") (pintype "bidirectional"))
    )
    (net (code "69") (name "unconnected-(U2-RI-Pad11)") (class "Default")
      (node (ref "U2") (pin "11") (pinfunction "RI_11") (pintype "bidirectional"))
    )
    (net (code "70") (name "unconnected-(U2-RS232-Pad15)") (class "Default")
      (node (ref "U2") (pin "15") (pinfunction "RS232_15") (pintype "bidirectional"))
    )
    (net (code "71") (name "unconnected-(U2-RTS-Pad14)") (class "Default")
      (node (ref "U2") (pin "14") (pinfunction "RTS_14") (pintype "bidirectional"))
    )
    (net (code "72") (name "unconnected-(U2-V3-Pad4)") (class "Default")
      (node (ref "U2") (pin "4") (pinfunction "V3_4") (pintype "bidirectional"))
    )
  )
)
